# KB_CTRL.net
KiCad netlist of a schematic drawn in Altium Designer
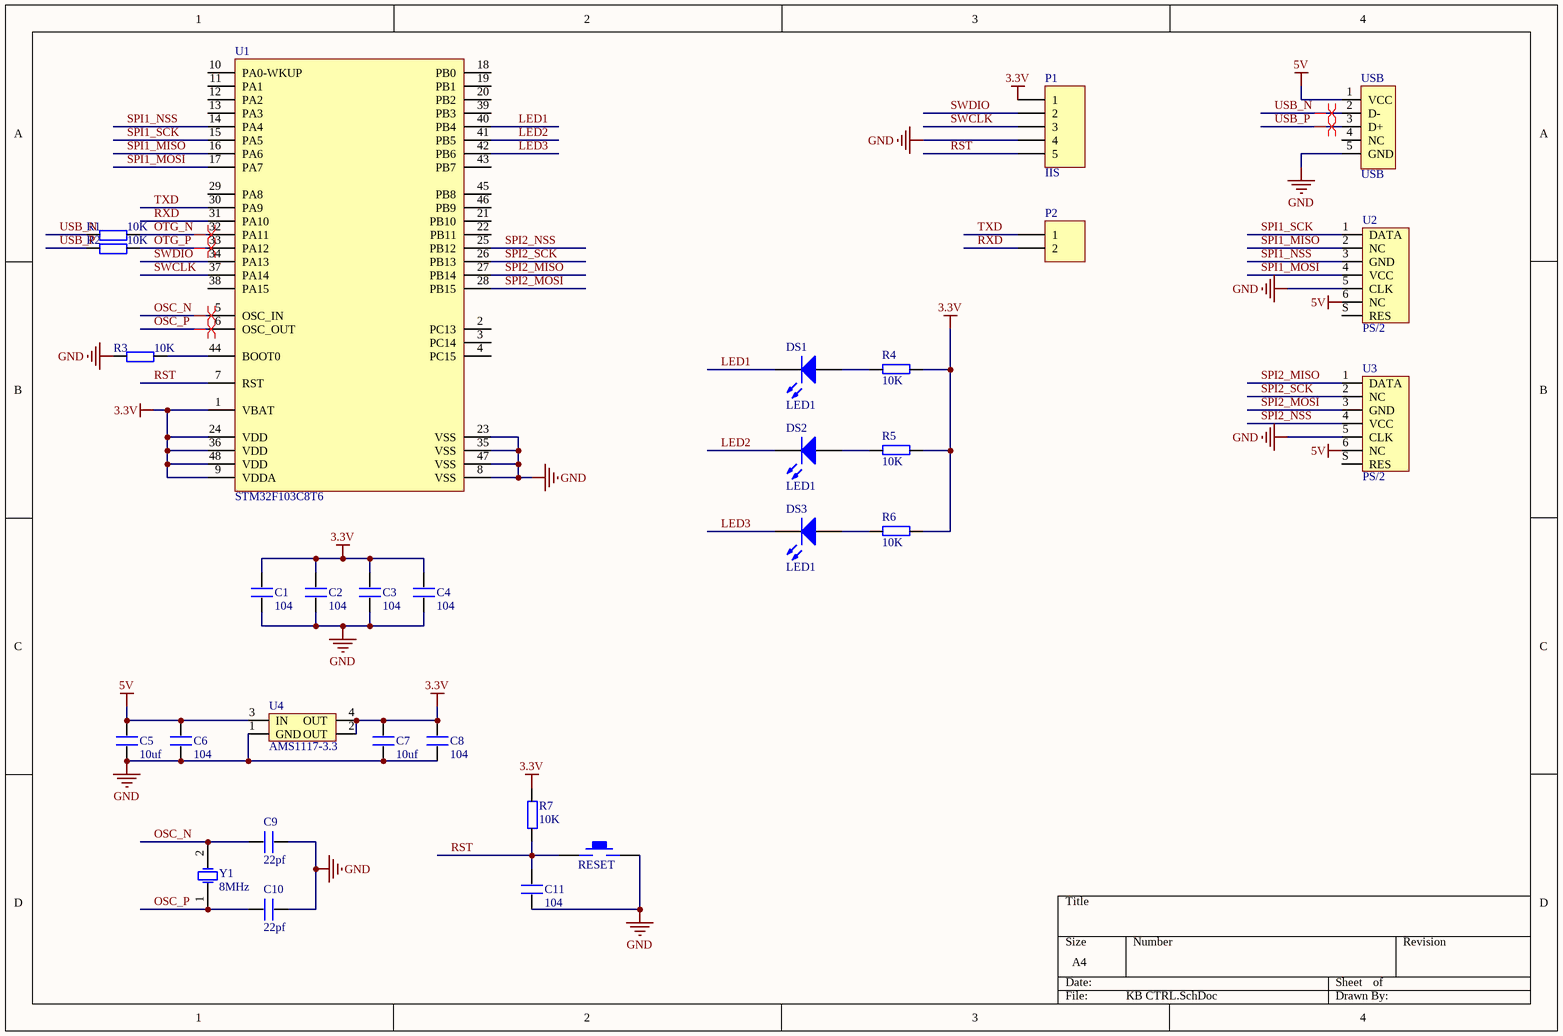
[diagram p0: KB CTRL.SchDoc]

(export (version "E")
  (design (tool "Eeschema 10.0.6"))
  (components
    (comp (ref "C1") (value "104") (footprint "0603P") (libsource (lib "战舰STM32开发板底板封装库") (part "C")))
    (comp (ref "C2") (value "104") (footprint "0603P") (libsource (lib "战舰STM32开发板底板封装库") (part "C")))
    (comp (ref "C3") (value "104") (footprint "0603P") (libsource (lib "战舰STM32开发板底板封装库") (part "C")))
    (comp (ref "C4") (value "104") (footprint "0603P") (libsource (lib "战舰STM32开发板底板封装库") (part "C")))
    (comp (ref "C5") (value "10uf") (footprint "0603P") (libsource (lib "Explorer STM32F407封装库") (part "C")))
    (comp (ref "C6") (value "104") (footprint "0603P") (libsource (lib "Explorer STM32F407封装库") (part "C")))
    (comp (ref "C7") (value "10uf") (footprint "0603P") (libsource (lib "Explorer STM32F407封装库") (part "C")))
    (comp (ref "C8") (value "104") (footprint "0603P") (libsource (lib "Explorer STM32F407封装库") (part "C")))
    (comp (ref "C9") (value "22pf") (footprint "0603P") (libsource (lib "战舰STM32开发板底板封装库") (part "C")))
    (comp (ref "C10") (value "22pf") (footprint "0603P") (libsource (lib "战舰STM32开发板底板封装库") (part "C")))
    (comp (ref "C11") (value "104") (footprint "0603P") (libsource (lib "战舰STM32开发板底板封装库") (part "C")))
    (comp (ref "DS1")
      (value "LED1")
      (footprint "0603P")
      (description "Typical RED, GREEN, YELLOW, AMBER GaAs LED")
      (fields (field (name "PUBLISHER") "Altium Limited"))
      (libsource (lib "战舰STM32开发板底板封装库") (part "LED2"))
    )
    (comp (ref "DS2")
      (value "LED1")
      (footprint "0603P")
      (description "Typical RED, GREEN, YELLOW, AMBER GaAs LED")
      (fields (field (name "PUBLISHER") "Altium Limited"))
      (libsource (lib "战舰STM32开发板底板封装库") (part "LED2"))
    )
    (comp (ref "DS3")
      (value "LED1")
      (footprint "0603P")
      (description "Typical RED, GREEN, YELLOW, AMBER GaAs LED")
      (fields (field (name "PUBLISHER") "Altium Limited"))
      (libsource (lib "战舰STM32开发板底板封装库") (part "LED2"))
    )
    (comp (ref "P1")
      (value "IIS")
      (footprint "HDR1X5")
      (description "Header, 5-Pin")
      (fields (field (name "PUBLISHER") "Altium Limited"))
      (libsource (lib "战舰STM32开发板底板封装库") (part "Header 5"))
    )
    (comp (ref "P2")
      (value "~")
      (footprint "HDR1X2")
      (description "Header, 2-Pin")
      (fields (field (name "PUBLISHER") "Altium Limited"))
      (libsource (lib "战舰STM32开发板底板封装库") (part "Header 2"))
    )
    (comp (ref "R1") (value "10K") (footprint "0603P") (libsource (lib "战舰STM32开发板底板封装库") (part "R")))
    (comp (ref "R2") (value "10K") (footprint "0603P") (libsource (lib "战舰STM32开发板底板封装库") (part "R")))
    (comp (ref "R3") (value "10K") (footprint "0603P") (libsource (lib "战舰STM32开发板底板封装库") (part "R")))
    (comp (ref "R4") (value "10K") (footprint "0603P") (libsource (lib "战舰STM32开发板底板封装库") (part "R")))
    (comp (ref "R5") (value "10K") (footprint "0603P") (libsource (lib "战舰STM32开发板底板封装库") (part "R")))
    (comp (ref "R6") (value "10K") (footprint "0603P") (libsource (lib "战舰STM32开发板底板封装库") (part "R")))
    (comp (ref "R7") (value "10K") (footprint "0603P") (libsource (lib "战舰STM32开发板底板封装库") (part "R")))
    (comp (ref "RESET")
      (value "KEY_M")
      (footprint "KEY_M")
      (libsource (lib "战舰STM32开发板底板封装库") (part "KEY_M"))
    )
    (comp (ref "U1")
      (value "STM32F103C8T6")
      (footprint "LQFP48")
      (libsource (lib "核心板") (part "STM32F103C8T6"))
    )
    (comp (ref "U2") (value "PS/2") (footprint "PS2-6PIN") (libsource (lib "战舰STM32开发板底板封装库") (part "P/S2")))
    (comp (ref "U3") (value "PS/2") (footprint "PS2-6PIN") (libsource (lib "战舰STM32开发板底板封装库") (part "P/S2")))
    (comp (ref "U4")
      (value "AMS1117-3.3")
      (footprint "AMS1117")
      (libsource (lib "Explorer STM32F407封装库") (part "AMS1117"))
    )
    (comp (ref "USB")
      (value "USB")
      (footprint "USB/SM0.8-6H5")
      (libsource (lib "战舰STM32开发板底板封装库") (part "USB5"))
    )
    (comp (ref "Y1")
      (value "8MHz")
      (footprint "XTAL_US")
      (description "Crystal Oscillator")
      (fields (field (name "PUBLISHER") "Altium Limited"))
      (libsource (lib "战舰STM32开发板底板封装库") (part "XTAL"))
    )
  )
  (nets
    (net (code "1") (name "/LED1") (class "Default")
      (node (ref "DS1") (pin "2") (pinfunction "K_2") (pintype "passive"))
      (node (ref "U1") (pin "40") (pinfunction "PB4_40") (pintype "passive"))
    )
    (net (code "2") (name "/LED2") (class "Default")
      (node (ref "DS2") (pin "2") (pinfunction "K_2") (pintype "passive"))
      (node (ref "U1") (pin "41") (pinfunction "PB5_41") (pintype "passive"))
    )
    (net (code "3") (name "/LED3") (class "Default")
      (node (ref "DS3") (pin "2") (pinfunction "K_2") (pintype "passive"))
      (node (ref "U1") (pin "42") (pinfunction "PB6_42") (pintype "passive"))
    )
    (net (code "4") (name "/OSC_N") (class "Default")
      (node (ref "C9") (pin "2") (pintype "passive"))
      (node (ref "U1") (pin "5") (pinfunction "OSC_IN_5") (pintype "passive"))
      (node (ref "Y1") (pin "2") (pinfunction "OSC2_2") (pintype "passive"))
    )
    (net (code "5") (name "/OSC_P") (class "Default")
      (node (ref "C10") (pin "2") (pintype "passive"))
      (node (ref "U1") (pin "6") (pinfunction "OSC_OUT_6") (pintype "passive"))
      (node (ref "Y1") (pin "1") (pinfunction "OSC1_1") (pintype "passive"))
    )
    (net (code "6") (name "/OTG_N") (class "Default")
      (node (ref "R1") (pin "2") (pintype "passive"))
      (node (ref "U1") (pin "32") (pinfunction "PA11_32") (pintype "passive"))
    )
    (net (code "7") (name "/OTG_P") (class "Default")
      (node (ref "R2") (pin "2") (pintype "passive"))
      (node (ref "U1") (pin "33") (pinfunction "PA12_33") (pintype "passive"))
    )
    (net (code "8") (name "/RST") (class "Default")
      (node (ref "C11") (pin "2") (pintype "passive"))
      (node (ref "P1") (pin "5") (pinfunction "5_5") (pintype "passive"))
      (node (ref "R7") (pin "1") (pintype "passive"))
      (node (ref "RESET") (pin "1") (pinfunction "1_1") (pintype "passive"))
      (node (ref "U1") (pin "7") (pinfunction "RST_7") (pintype "passive"))
    )
    (net (code "9") (name "/RXD") (class "Default")
      (node (ref "P2") (pin "2") (pinfunction "2_2") (pintype "passive"))
      (node (ref "U1") (pin "31") (pinfunction "PA10_31") (pintype "passive"))
    )
    (net (code "10") (name "/SPI1_MISO") (class "Default")
      (node (ref "U1") (pin "16") (pinfunction "PA6_16") (pintype "passive"))
      (node (ref "U2") (pin "2") (pinfunction "NC_2") (pintype "passive"))
    )
    (net (code "11") (name "/SPI1_MOSI") (class "Default")
      (node (ref "U1") (pin "17") (pinfunction "PA7_17") (pintype "passive"))
      (node (ref "U2") (pin "4") (pinfunction "VCC_4") (pintype "passive"))
    )
    (net (code "12") (name "/SPI1_NSS") (class "Default")
      (node (ref "U1") (pin "14") (pinfunction "PA4_14") (pintype "passive"))
      (node (ref "U2") (pin "3") (pinfunction "GND_3") (pintype "passive"))
    )
    (net (code "13") (name "/SPI1_SCK") (class "Default")
      (node (ref "U1") (pin "15") (pinfunction "PA5_15") (pintype "passive"))
      (node (ref "U2") (pin "1") (pinfunction "DATA_1") (pintype "passive"))
    )
    (net (code "14") (name "/SPI2_MISO") (class "Default")
      (node (ref "U1") (pin "27") (pinfunction "PB14_27") (pintype "passive"))
      (node (ref "U3") (pin "1") (pinfunction "DATA_1") (pintype "passive"))
    )
    (net (code "15") (name "/SPI2_MOSI") (class "Default")
      (node (ref "U1") (pin "28") (pinfunction "PB15_28") (pintype "passive"))
      (node (ref "U3") (pin "3") (pinfunction "GND_3") (pintype "passive"))
    )
    (net (code "16") (name "/SPI2_NSS") (class "Default")
      (node (ref "U1") (pin "25") (pinfunction "PB12_25") (pintype "passive"))
      (node (ref "U3") (pin "4") (pinfunction "VCC_4") (pintype "passive"))
    )
    (net (code "17") (name "/SPI2_SCK") (class "Default")
      (node (ref "U1") (pin "26") (pinfunction "PB13_26") (pintype "passive"))
      (node (ref "U3") (pin "2") (pinfunction "NC_2") (pintype "passive"))
    )
    (net (code "18") (name "/SWCLK") (class "Default")
      (node (ref "P1") (pin "3") (pinfunction "3_3") (pintype "passive"))
      (node (ref "U1") (pin "37") (pinfunction "PA14_37") (pintype "passive"))
    )
    (net (code "19") (name "/SWDIO") (class "Default")
      (node (ref "P1") (pin "2") (pinfunction "2_2") (pintype "passive"))
      (node (ref "U1") (pin "34") (pinfunction "PA13_34") (pintype "passive"))
    )
    (net (code "20") (name "/TXD") (class "Default")
      (node (ref "P2") (pin "1") (pinfunction "1_1") (pintype "passive"))
      (node (ref "U1") (pin "30") (pinfunction "PA9_30") (pintype "passive"))
    )
    (net (code "21") (name "/USB_N") (class "Default")
      (node (ref "R1") (pin "1") (pintype "passive"))
      (node (ref "USB") (pin "2") (pinfunction "D-_2") (pintype "passive"))
    )
    (net (code "22") (name "/USB_P") (class "Default")
      (node (ref "R2") (pin "1") (pintype "passive"))
      (node (ref "USB") (pin "3") (pinfunction "D+_3") (pintype "passive"))
    )
    (net (code "23") (name "3.3V") (class "Default")
      (node (ref "C1") (pin "2") (pintype "passive"))
      (node (ref "C2") (pin "2") (pintype "passive"))
      (node (ref "C3") (pin "2") (pintype "passive"))
      (node (ref "C4") (pin "2") (pintype "passive"))
      (node (ref "C7") (pin "2") (pintype "passive"))
      (node (ref "C8") (pin "2") (pintype "passive"))
      (node (ref "P1") (pin "1") (pinfunction "1_1") (pintype "passive"))
      (node (ref "R4") (pin "1") (pintype "passive"))
      (node (ref "R5") (pin "1") (pintype "passive"))
      (node (ref "R6") (pin "1") (pintype "passive"))
      (node (ref "R7") (pin "2") (pintype "passive"))
      (node (ref "U1") (pin "1") (pinfunction "VBAT_1") (pintype "passive"))
      (node (ref "U1") (pin "24") (pinfunction "VDD_24") (pintype "passive"))
      (node (ref "U1") (pin "36") (pinfunction "VDD_36") (pintype "passive"))
      (node (ref "U1") (pin "48") (pinfunction "VDD_48") (pintype "passive"))
      (node (ref "U1") (pin "9") (pinfunction "VDDA_9") (pintype "passive"))
      (node (ref "U4") (pin "2") (pinfunction "OUT_2") (pintype "passive"))
      (node (ref "U4") (pin "4") (pinfunction "OUT_4") (pintype "passive"))
    )
    (net (code "24") (name "5V") (class "Default")
      (node (ref "C5") (pin "2") (pintype "passive"))
      (node (ref "C6") (pin "2") (pintype "passive"))
      (node (ref "U2") (pin "6") (pinfunction "NC_6") (pintype "passive"))
      (node (ref "U3") (pin "6") (pinfunction "NC_6") (pintype "passive"))
      (node (ref "U4") (pin "3") (pinfunction "IN_3") (pintype "passive"))
      (node (ref "USB") (pin "1") (pinfunction "VCC_1") (pintype "passive"))
    )
    (net (code "25") (name "GND") (class "Default")
      (node (ref "C1") (pin "1") (pintype "passive"))
      (node (ref "C10") (pin "1") (pintype "passive"))
      (node (ref "C11") (pin "1") (pintype "passive"))
      (node (ref "C2") (pin "1") (pintype "passive"))
      (node (ref "C3") (pin "1") (pintype "passive"))
      (node (ref "C4") (pin "1") (pintype "passive"))
      (node (ref "C5") (pin "1") (pintype "passive"))
      (node (ref "C6") (pin "1") (pintype "passive"))
      (node (ref "C7") (pin "1") (pintype "passive"))
      (node (ref "C8") (pin "1") (pintype "passive"))
      (node (ref "C9") (pin "1") (pintype "passive"))
      (node (ref "P1") (pin "4") (pinfunction "4_4") (pintype "passive"))
      (node (ref "R3") (pin "1") (pintype "passive"))
      (node (ref "RESET") (pin "2") (pinfunction "2_2") (pintype "passive"))
      (node (ref "U1") (pin "23") (pinfunction "VSS_23") (pintype "passive"))
      (node (ref "U1") (pin "35") (pinfunction "VSS_35") (pintype "passive"))
      (node (ref "U1") (pin "47") (pinfunction "VSS_47") (pintype "passive"))
      (node (ref "U1") (pin "8") (pinfunction "VSS_8") (pintype "passive"))
      (node (ref "U2") (pin "5") (pinfunction "CLK_5") (pintype "passive"))
      (node (ref "U3") (pin "5") (pinfunction "CLK_5") (pintype "passive"))
      (node (ref "U4") (pin "1") (pinfunction "GND_1") (pintype "passive"))
      (node (ref "USB") (pin "5") (pinfunction "GND_5") (pintype "passive"))
    )
    (net (code "26") (name "Net-(DS1-A)") (class "Default")
      (node (ref "DS1") (pin "1") (pinfunction "A_1") (pintype "passive"))
      (node (ref "R4") (pin "2") (pintype "passive"))
    )
    (net (code "27") (name "Net-(DS2-A)") (class "Default")
      (node (ref "DS2") (pin "1") (pinfunction "A_1") (pintype "passive"))
      (node (ref "R5") (pin "2") (pintype "passive"))
    )
    (net (code "28") (name "Net-(DS3-A)") (class "Default")
      (node (ref "DS3") (pin "1") (pinfunction "A_1") (pintype "passive"))
      (node (ref "R6") (pin "2") (pintype "passive"))
    )
    (net (code "29") (name "Net-(U1-BOOT0)") (class "Default")
      (node (ref "R3") (pin "2") (pintype "passive"))
      (node (ref "U1") (pin "44") (pinfunction "BOOT0_44") (pintype "passive"))
    )
    (net (code "30") (name "unconnected-(U1-PA0-WKUP-Pad10)") (class "Default")
      (node (ref "U1") (pin "10") (pinfunction "PA0-WKUP_10") (pintype "passive"))
    )
    (net (code "31") (name "unconnected-(U1-PA1-Pad11)") (class "Default")
      (node (ref "U1") (pin "11") (pinfunction "PA1_11") (pintype "passive"))
    )
    (net (code "32") (name "unconnected-(U1-PA2-Pad12)") (class "Default")
      (node (ref "U1") (pin "12") (pinfunction "PA2_12") (pintype "passive"))
    )
    (net (code "33") (name "unconnected-(U1-PA3-Pad13)") (class "Default")
      (node (ref "U1") (pin "13") (pinfunction "PA3_13") (pintype "passive"))
    )
    (net (code "34") (name "unconnected-(U1-PA8-Pad29)") (class "Default")
      (node (ref "U1") (pin "29") (pinfunction "PA8_29") (pintype "passive"))
    )
    (net (code "35") (name "unconnected-(U1-PA15-Pad38)") (class "Default")
      (node (ref "U1") (pin "38") (pinfunction "PA15_38") (pintype "passive"))
    )
    (net (code "36") (name "unconnected-(U1-PB0-Pad18)") (class "Default")
      (node (ref "U1") (pin "18") (pinfunction "PB0_18") (pintype "passive"))
    )
    (net (code "37") (name "unconnected-(U1-PB1-Pad19)") (class "Default")
      (node (ref "U1") (pin "19") (pinfunction "PB1_19") (pintype "passive"))
    )
    (net (code "38") (name "unconnected-(U1-PB2-Pad20)") (class "Default")
      (node (ref "U1") (pin "20") (pinfunction "PB2_20") (pintype "passive"))
    )
    (net (code "39") (name "unconnected-(U1-PB3-Pad39)") (class "Default")
      (node (ref "U1") (pin "39") (pinfunction "PB3_39") (pintype "passive"))
    )
    (net (code "40") (name "unconnected-(U1-PB7-Pad43)") (class "Default")
      (node (ref "U1") (pin "43") (pinfunction "PB7_43") (pintype "passive"))
    )
    (net (code "41") (name "unconnected-(U1-PB8-Pad45)") (class "Default")
      (node (ref "U1") (pin "45") (pinfunction "PB8_45") (pintype "passive"))
    )
    (net (code "42") (name "unconnected-(U1-PB9-Pad46)") (class "Default")
      (node (ref "U1") (pin "46") (pinfunction "PB9_46") (pintype "passive"))
    )
    (net (code "43") (name "unconnected-(U1-PB10-Pad21)") (class "Default")
      (node (ref "U1") (pin "21") (pinfunction "PB10_21") (pintype "passive"))
    )
    (net (code "44") (name "unconnected-(U1-PB11-Pad22)") (class "Default")
      (node (ref "U1") (pin "22") (pinfunction "PB11_22") (pintype "passive"))
    )
    (net (code "45") (name "unconnected-(U1-PC13-Pad2)") (class "Default")
      (node (ref "U1") (pin "2") (pinfunction "PC13_2") (pintype "passive"))
    )
    (net (code "46") (name "unconnected-(U1-PC14-Pad3)") (class "Default")
      (node (ref "U1") (pin "3") (pinfunction "PC14_3") (pintype "passive"))
    )
    (net (code "47") (name "unconnected-(U1-PC15-Pad4)") (class "Default")
      (node (ref "U1") (pin "4") (pinfunction "PC15_4") (pintype "passive"))
    )
    (net (code "48") (name "unconnected-(U2-RES-PadS)") (class "Default")
      (node (ref "U2") (pin "S") (pinfunction "RES_S") (pintype "passive"))
    )
    (net (code "49") (name "unconnected-(U3-RES-PadS)") (class "Default")
      (node (ref "U3") (pin "S") (pinfunction "RES_S") (pintype "passive"))
    )
    (net (code "50") (name "unconnected-(USB-NC-Pad4)") (class "Default")
      (node (ref "USB") (pin "4") (pinfunction "NC_4") (pintype "passive"))
    )
  )
)
